# Node_Controller_v2.net
KiCad netlist of a schematic drawn in Altium Designer
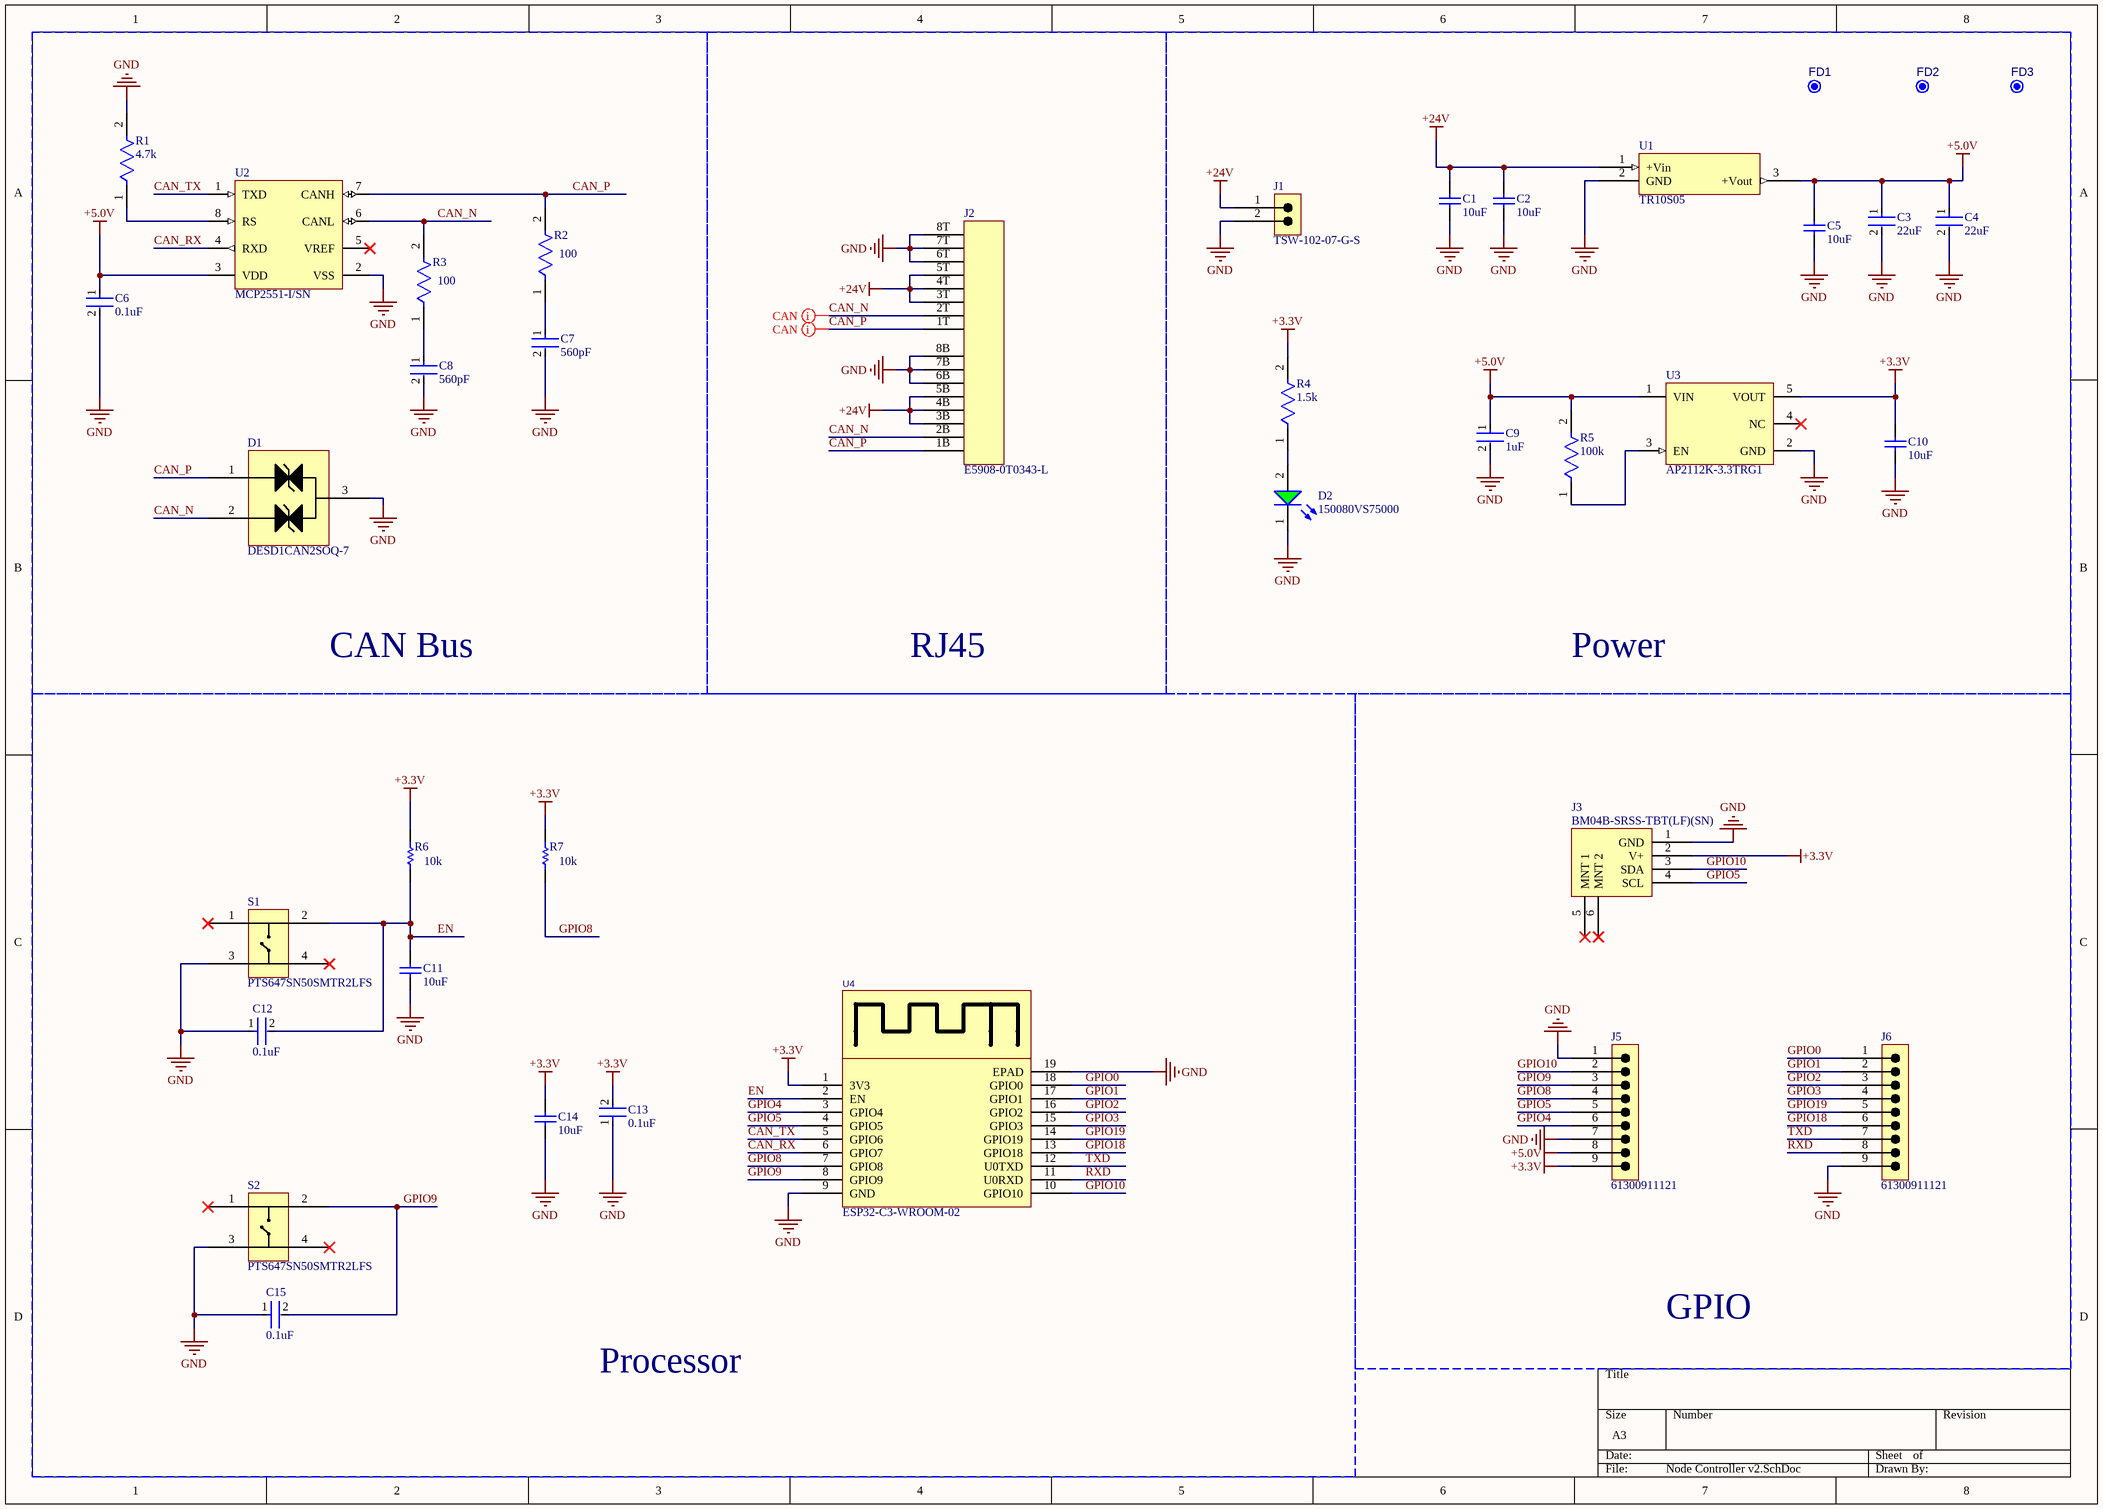
[diagram p0: Node Controller v2.SchDoc]

(export (version "E")
  (design (tool "Eeschema 10.0.6"))
  (components
    (comp (ref "C1")
      (value "10uF")
      (footprint "CAPC2013X145X50ML20T25")
      (libsource (lib "C0514760 C0514760") (part "CAP-NP-2"))
    )
    (comp (ref "C2")
      (value "10uF")
      (footprint "CAPC2013X145X50ML20T25")
      (libsource (lib "C0514760 C0514760") (part "CAP-NP-2"))
    )
    (comp (ref "C3")
      (value "22uF")
      (footprint "FP-GMC21R-IPC_B")
      (libsource (lib "C0514760 C0514760") (part "b4654b650e69147ec39a6b967a45e02"))
    )
    (comp (ref "C4")
      (value "22uF")
      (footprint "FP-GMC21R-IPC_B")
      (libsource (lib "C0514760 C0514760") (part "b4654b650e69147ec39a6b967a45e02"))
    )
    (comp (ref "C5")
      (value "10uF")
      (footprint "CAPC2013X145X50ML20T25")
      (libsource (lib "C0514760 C0514760") (part "CAP-NP-2"))
    )
    (comp (ref "C6")
      (value "0.1uF")
      (footprint "FP-CC0603-DA-IPC_A")
      (libsource (lib "C0514760 C0514760") (part "11868f565c42a9108669ba33697ecf6"))
    )
    (comp (ref "C7")
      (value "560pF")
      (footprint "FP-CC0805-0_85-IPC_A")
      (libsource (lib "C0514760 C0514760") (part "11868f565c42a9108669ba33697ecf6"))
    )
    (comp (ref "C8")
      (value "560pF")
      (footprint "FP-CC0805-0_85-IPC_A")
      (libsource (lib "C0514760 C0514760") (part "11868f565c42a9108669ba33697ecf6"))
    )
    (comp (ref "C9")
      (value "1uF")
      (footprint "FP-CL21-IPC_A")
      (libsource (lib "C0514760 C0514760") (part "b4654b650e69147ec39a6b967a45e02"))
    )
    (comp (ref "C10")
      (value "10uF")
      (footprint "CAPC2013X145X50ML20T25")
      (libsource (lib "C0514760 C0514760") (part "CAP-NP-2"))
    )
    (comp (ref "C11")
      (value "10uF")
      (footprint "CAPC2013X145X50ML20T25")
      (libsource (lib "C0514760 C0514760") (part "CAP-NP-2"))
    )
    (comp (ref "C12")
      (value "0.1uF")
      (footprint "FP-CC0603-DA-IPC_A")
      (libsource (lib "C0514760 C0514760") (part "11868f565c42a9108669ba33697ecf6"))
    )
    (comp (ref "C13")
      (value "0.1uF")
      (footprint "FP-CC0603-DA-IPC_A")
      (libsource (lib "C0514760 C0514760") (part "11868f565c42a9108669ba33697ecf6"))
    )
    (comp (ref "C14")
      (value "10uF")
      (footprint "CAPC2013X145X50ML20T25")
      (libsource (lib "C0514760 C0514760") (part "CAP-NP-2"))
    )
    (comp (ref "C15")
      (value "0.1uF")
      (footprint "FP-CC0603-DA-IPC_A")
      (libsource (lib "C0514760 C0514760") (part "11868f565c42a9108669ba33697ecf6"))
    )
    (comp (ref "D1")
      (value "DESD1CAN2SOQ-7")
      (footprint "SOT95P245X110-3N")
      (description "Trans Voltage Suppressor Diode, 200W, 24V V(RWM), Bidirectional, 2 Element, Silicon")
      (libsource (lib "C0514760 C0514760") (part "DESD1CAN2SOQ-7-Symbol-1"))
    )
    (comp (ref "D2")
      (value "150080VS75000")
      (footprint "WL-SMCW_0805_150080xx75000")
      (description "Single Color LED, Bright Green, Water Clear, 1.4mm")
      (libsource (lib "C0514760 C0514760") (part "LED_Green_2A-1K"))
    )
    (comp (ref "FD1")
      (value "JLC FID1X2R")
      (footprint "FID1X2R")
      (description "Fiducial - Round 1x2mm")
      (libsource (lib "C0514760 C0514760") (part "CMP-00134-2"))
    )
    (comp (ref "FD2")
      (value "JLC FID1X2R")
      (footprint "FID1X2R")
      (description "Fiducial - Round 1x2mm")
      (libsource (lib "C0514760 C0514760") (part "CMP-00134-2"))
    )
    (comp (ref "FD3")
      (value "JLC FID1X2R")
      (footprint "FID1X2R")
      (description "Fiducial - Round 1x2mm")
      (libsource (lib "C0514760 C0514760") (part "CMP-00134-2"))
    )
    (comp (ref "J1")
      (value "TSW-102-07-G-S")
      (footprint "FP-TSW-102-07-G-S-MFG")
      (libsource (lib "C0514760 C0514760") (part "3bc925449376181038e59eaffc5286c"))
    )
    (comp (ref "J2")
      (value "E5908-0T0343-L")
      (footprint "E5908-0T0343-L-Footprint-1")
      (description "Telecom and Datacom Connector, 16 Contact(s), Female, Right Angle, Solder Terminal, Jack")
      (libsource (lib "C0514760 C0514760") (part "E5908-0T0343-L-Symbol-1"))
    )
    (comp (ref "J3")
      (value "BM04B-SRSS-TBT(LF)(SN)")
      (footprint "FP-BM04B-SRSS-TBT_LF_SN-MFG")
      (description "1.0mm Pitch, Ultra-Compact, Low Profile Design, Interchangeable Shrouded Header")
      (libsource (lib "C0514760 C0514760") (part "8e3688c4b118bffc0dd9b7401e414ba"))
    )
    (comp (ref "J5")
      (value "61300911121")
      (footprint "61300911121")
      (libsource (lib "C0514760 C0514760") (part "Header_Male_1R_09P"))
    )
    (comp (ref "J6")
      (value "61300911121")
      (footprint "61300911121")
      (libsource (lib "C0514760 C0514760") (part "Header_Male_1R_09P"))
    )
    (comp (ref "R1")
      (value "4.7k")
      (footprint "FP-RT0805-IPC_A")
      (description "Fixed Resistor, Thin Film, 0.125W, 4700ohm, 150V, 1% +/-Tol, 50ppm/Cel, Surface Mount, 0805")
      (fields (field (name "TOLERANCE") "1%") (field (name "POWER") "125mW"))
      (libsource (lib "C0514760 C0514760") (part "1029c3af85768c4190bb7ad29bc67b5"))
    )
    (comp (ref "R2")
      (value "100")
      (footprint "FP-RT0805-0_6-IPC_A")
      (description "Fixed Resistor, Thin Film, 0.125W, 100ohm, 150V, 0.1% +/-Tol, 25ppm/Cel, Surface Mount, 0805")
      (fields (field (name "POWER") "125mW") (field (name "TOLERANCE") "0.1%"))
      (libsource (lib "C0514760 C0514760") (part "1029c3af85768c4190bb7ad29bc67b5"))
    )
    (comp (ref "R3")
      (value "100")
      (footprint "FP-RT0805-0_6-IPC_A")
      (description "Fixed Resistor, Thin Film, 0.125W, 100ohm, 150V, 0.1% +/-Tol, 25ppm/Cel, Surface Mount, 0805")
      (fields (field (name "POWER") "125mW") (field (name "TOLERANCE") "0.1%"))
      (libsource (lib "C0514760 C0514760") (part "1029c3af85768c4190bb7ad29bc67b5"))
    )
    (comp (ref "R4")
      (value "1.5k")
      (footprint "FP-RT0805-IPC_A")
      (description "Fixed Resistor, Thin Film, 0.125W, 1500ohm, 150V, 1% +/-Tol, 50ppm/Cel, Surface Mount, 0805")
      (fields (field (name "POWER") "125mW") (field (name "TOLERANCE") "1%"))
      (libsource (lib "C0514760 C0514760") (part "1029c3af85768c4190bb7ad29bc67b5"))
    )
    (comp (ref "R5")
      (value "100k")
      (footprint "FP-RT0805-IPC_A")
      (description "Fixed Resistor, Thin Film, 0.125W, 100000ohm, 150V, 1% +/-Tol, 50ppm/Cel, Surface Mount, 0805")
      (fields (field (name "TOLERANCE") "1%") (field (name "POWER") "125mW"))
      (libsource (lib "C0514760 C0514760") (part "1029c3af85768c4190bb7ad29bc67b5"))
    )
    (comp (ref "R6")
      (value "10k")
      (footprint "RESC2013X60X35ML10T20")
      (fields (field (name "TOLERANCE") "1%") (field (name "POWER") "125mW"))
      (libsource (lib "C0514760 C0514760") (part "RES"))
    )
    (comp (ref "R7")
      (value "10k")
      (footprint "RESC2013X60X35ML10T20")
      (fields (field (name "TOLERANCE") "1%") (field (name "POWER") "125mW"))
      (libsource (lib "C0514760 C0514760") (part "RES"))
    )
    (comp (ref "S1")
      (value "PTS647SN50SMTR2LFS")
      (footprint "PTS647SN50SMTR2LFS-Footprint-1")
      (libsource (lib "C0514760 C0514760") (part "PTS647SN50SMTR2LFS-Symbol-1"))
    )
    (comp (ref "S2")
      (value "PTS647SN50SMTR2LFS")
      (footprint "PTS647SN50SMTR2LFS-Footprint-1")
      (libsource (lib "C0514760 C0514760") (part "PTS647SN50SMTR2LFS-Symbol-1"))
    )
    (comp (ref "U1")
      (value "TR10S05")
      (footprint "TR10S05-Footprint-1")
      (description "DC-DC Regulated Power Supply Module")
      (libsource (lib "C0514760 C0514760") (part "TR10S05-Symbol-1"))
    )
    (comp (ref "U2")
      (value "MCP2551-I/SN")
      (footprint "MCHP-SN8_V")
      (description "CAN Transceiver, 1-Trnsvr, PDSO8")
      (libsource (lib "C0514760 C0514760") (part "MCHP-MCP2551-SN8"))
    )
    (comp (ref "U3")
      (value "AP2112K-3.3TRG1")
      (footprint "FP-SOT25-IPC_B")
      (description "Fixed Positive LDO Regulator, 3.3V, 0.4V Dropout, CMOS, PDSO5")
      (libsource (lib "C0514760 C0514760") (part "c8ab751aee5229183125ab046a11caa"))
    )
    (comp (ref "U4")
      (value "ESP32-C3-WROOM-02")
      (footprint "ESP32-C3-WROOM-02")
      (libsource (lib "C0514760 C0514760") (part "ESP32-C3-WROOM-02"))
    )
  )
  (nets
    (net (code "1") (name "+3.3V") (class "Default")
      (node (ref "C10") (pin "2") (pinfunction "2_2") (pintype "passive"))
      (node (ref "C13") (pin "2") (pinfunction "2_2") (pintype "passive"))
      (node (ref "C14") (pin "2") (pinfunction "2_2") (pintype "passive"))
      (node (ref "J3") (pin "2") (pinfunction "V+_2") (pintype "passive"))
      (node (ref "J5") (pin "9") (pinfunction "9_9") (pintype "passive"))
      (node (ref "R4") (pin "2") (pinfunction "2_2") (pintype "passive"))
      (node (ref "R6") (pin "2") (pinfunction "2_2") (pintype "passive"))
      (node (ref "R7") (pin "2") (pinfunction "2_2") (pintype "passive"))
      (node (ref "U3") (pin "5") (pinfunction "VOUT_5") (pintype "power_in"))
      (node (ref "U4") (pin "1") (pinfunction "3V3_1") (pintype "passive"))
    )
    (net (code "2") (name "+5.0V") (class "Default")
      (node (ref "C3") (pin "1") (pinfunction "1_1") (pintype "passive"))
      (node (ref "C4") (pin "1") (pinfunction "1_1") (pintype "passive"))
      (node (ref "C5") (pin "2") (pinfunction "2_2") (pintype "passive"))
      (node (ref "C6") (pin "1") (pinfunction "1_1") (pintype "passive"))
      (node (ref "C9") (pin "1") (pinfunction "1_1") (pintype "passive"))
      (node (ref "J5") (pin "8") (pinfunction "8_8") (pintype "passive"))
      (node (ref "R5") (pin "2") (pinfunction "2_2") (pintype "passive"))
      (node (ref "U1") (pin "3") (pinfunction "+Vout_3") (pintype "output"))
      (node (ref "U2") (pin "3") (pinfunction "VDD_3") (pintype "power_in"))
      (node (ref "U3") (pin "1") (pinfunction "VIN_1") (pintype "power_in"))
    )
    (net (code "3") (name "+24V") (class "Default")
      (node (ref "C1") (pin "2") (pinfunction "2_2") (pintype "passive"))
      (node (ref "C2") (pin "2") (pinfunction "2_2") (pintype "passive"))
      (node (ref "J1") (pin "1") (pinfunction "1_1") (pintype "passive"))
      (node (ref "J2") (pin "3B") (pinfunction "3B_3B") (pintype "passive"))
      (node (ref "J2") (pin "3T") (pinfunction "3T_3T") (pintype "passive"))
      (node (ref "J2") (pin "4B") (pinfunction "4B_4B") (pintype "passive"))
      (node (ref "J2") (pin "4T") (pinfunction "4T_4T") (pintype "passive"))
      (node (ref "J2") (pin "5B") (pinfunction "5B_5B") (pintype "passive"))
      (node (ref "J2") (pin "5T") (pinfunction "5T_5T") (pintype "passive"))
      (node (ref "U1") (pin "1") (pinfunction "+Vin_1") (pintype "input"))
    )
    (net (code "4") (name "/CAN_N") (class "Default")
      (node (ref "D1") (pin "2") (pinfunction "2_2") (pintype "passive"))
      (node (ref "J2") (pin "2B") (pinfunction "2B_2B") (pintype "passive"))
      (node (ref "J2") (pin "2T") (pinfunction "2T_2T") (pintype "passive"))
      (node (ref "R3") (pin "2") (pinfunction "2_2") (pintype "passive"))
      (node (ref "U2") (pin "6") (pinfunction "CANL_6") (pintype "bidirectional"))
    )
    (net (code "5") (name "/CAN_P") (class "Default")
      (node (ref "D1") (pin "1") (pinfunction "1_1") (pintype "passive"))
      (node (ref "J2") (pin "1B") (pinfunction "1B_1B") (pintype "passive"))
      (node (ref "J2") (pin "1T") (pinfunction "1T_1T") (pintype "passive"))
      (node (ref "R2") (pin "2") (pinfunction "2_2") (pintype "passive"))
      (node (ref "U2") (pin "7") (pinfunction "CANH_7") (pintype "bidirectional"))
    )
    (net (code "6") (name "/CAN_RX") (class "Default")
      (node (ref "U2") (pin "4") (pinfunction "RXD_4") (pintype "output"))
      (node (ref "U4") (pin "6") (pinfunction "GPIO7_6") (pintype "passive"))
    )
    (net (code "7") (name "/CAN_TX") (class "Default")
      (node (ref "U2") (pin "1") (pinfunction "TXD_1") (pintype "input"))
      (node (ref "U4") (pin "5") (pinfunction "GPIO6_5") (pintype "passive"))
    )
    (net (code "8") (name "/EN") (class "Default")
      (node (ref "C11") (pin "2") (pinfunction "2_2") (pintype "passive"))
      (node (ref "C12") (pin "2") (pinfunction "2_2") (pintype "passive"))
      (node (ref "R6") (pin "1") (pinfunction "1_1") (pintype "passive"))
      (node (ref "S1") (pin "2") (pinfunction "2_2") (pintype "passive"))
      (node (ref "U4") (pin "2") (pinfunction "EN_2") (pintype "passive"))
    )
    (net (code "9") (name "/GPIO0") (class "Default")
      (node (ref "J6") (pin "1") (pinfunction "1_1") (pintype "passive"))
      (node (ref "U4") (pin "18") (pinfunction "GPIO0_18") (pintype "passive"))
    )
    (net (code "10") (name "/GPIO1") (class "Default")
      (node (ref "J6") (pin "2") (pinfunction "2_2") (pintype "passive"))
      (node (ref "U4") (pin "17") (pinfunction "GPIO1_17") (pintype "passive"))
    )
    (net (code "11") (name "/GPIO2") (class "Default")
      (node (ref "J6") (pin "3") (pinfunction "3_3") (pintype "passive"))
      (node (ref "U4") (pin "16") (pinfunction "GPIO2_16") (pintype "passive"))
    )
    (net (code "12") (name "/GPIO3") (class "Default")
      (node (ref "J6") (pin "4") (pinfunction "4_4") (pintype "passive"))
      (node (ref "U4") (pin "15") (pinfunction "GPIO3_15") (pintype "passive"))
    )
    (net (code "13") (name "/GPIO4") (class "Default")
      (node (ref "J5") (pin "6") (pinfunction "6_6") (pintype "passive"))
      (node (ref "U4") (pin "3") (pinfunction "GPIO4_3") (pintype "passive"))
    )
    (net (code "14") (name "/GPIO5") (class "Default")
      (node (ref "J3") (pin "4") (pinfunction "SCL_4") (pintype "passive"))
      (node (ref "J5") (pin "5") (pinfunction "5_5") (pintype "passive"))
      (node (ref "U4") (pin "4") (pinfunction "GPIO5_4") (pintype "passive"))
    )
    (net (code "15") (name "/GPIO8") (class "Default")
      (node (ref "J5") (pin "4") (pinfunction "4_4") (pintype "passive"))
      (node (ref "R7") (pin "1") (pinfunction "1_1") (pintype "passive"))
      (node (ref "U4") (pin "7") (pinfunction "GPIO8_7") (pintype "passive"))
    )
    (net (code "16") (name "/GPIO9") (class "Default")
      (node (ref "C15") (pin "2") (pinfunction "2_2") (pintype "passive"))
      (node (ref "J5") (pin "3") (pinfunction "3_3") (pintype "passive"))
      (node (ref "S2") (pin "2") (pinfunction "2_2") (pintype "passive"))
      (node (ref "U4") (pin "8") (pinfunction "GPIO9_8") (pintype "passive"))
    )
    (net (code "17") (name "/GPIO10") (class "Default")
      (node (ref "J3") (pin "3") (pinfunction "SDA_3") (pintype "passive"))
      (node (ref "J5") (pin "2") (pinfunction "2_2") (pintype "passive"))
      (node (ref "U4") (pin "10") (pinfunction "GPIO10_10") (pintype "passive"))
    )
    (net (code "18") (name "/GPIO18") (class "Default")
      (node (ref "J6") (pin "6") (pinfunction "6_6") (pintype "passive"))
      (node (ref "U4") (pin "13") (pinfunction "GPIO18_13") (pintype "passive"))
    )
    (net (code "19") (name "/GPIO19") (class "Default")
      (node (ref "J6") (pin "5") (pinfunction "5_5") (pintype "passive"))
      (node (ref "U4") (pin "14") (pinfunction "GPIO19_14") (pintype "passive"))
    )
    (net (code "20") (name "/RXD") (class "Default")
      (node (ref "J6") (pin "8") (pinfunction "8_8") (pintype "passive"))
      (node (ref "U4") (pin "11") (pinfunction "U0RXD_11") (pintype "passive"))
    )
    (net (code "21") (name "/TXD") (class "Default")
      (node (ref "J6") (pin "7") (pinfunction "7_7") (pintype "passive"))
      (node (ref "U4") (pin "12") (pinfunction "U0TXD_12") (pintype "passive"))
    )
    (net (code "22") (name "GND") (class "Default")
      (node (ref "C1") (pin "1") (pinfunction "1_1") (pintype "passive"))
      (node (ref "C10") (pin "1") (pinfunction "1_1") (pintype "passive"))
      (node (ref "C11") (pin "1") (pinfunction "1_1") (pintype "passive"))
      (node (ref "C12") (pin "1") (pinfunction "1_1") (pintype "passive"))
      (node (ref "C13") (pin "1") (pinfunction "1_1") (pintype "passive"))
      (node (ref "C14") (pin "1") (pinfunction "1_1") (pintype "passive"))
      (node (ref "C15") (pin "1") (pinfunction "1_1") (pintype "passive"))
      (node (ref "C2") (pin "1") (pinfunction "1_1") (pintype "passive"))
      (node (ref "C3") (pin "2") (pinfunction "2_2") (pintype "passive"))
      (node (ref "C4") (pin "2") (pinfunction "2_2") (pintype "passive"))
      (node (ref "C5") (pin "1") (pinfunction "1_1") (pintype "passive"))
      (node (ref "C6") (pin "2") (pinfunction "2_2") (pintype "passive"))
      (node (ref "C7") (pin "2") (pinfunction "2_2") (pintype "passive"))
      (node (ref "C8") (pin "2") (pinfunction "2_2") (pintype "passive"))
      (node (ref "C9") (pin "2") (pinfunction "2_2") (pintype "passive"))
      (node (ref "D1") (pin "3") (pinfunction "3_3") (pintype "passive"))
      (node (ref "D2") (pin "1") (pinfunction "K_1") (pintype "passive"))
      (node (ref "J1") (pin "2") (pinfunction "2_2") (pintype "passive"))
      (node (ref "J2") (pin "6B") (pinfunction "6B_6B") (pintype "passive"))
      (node (ref "J2") (pin "6T") (pinfunction "6T_6T") (pintype "passive"))
      (node (ref "J2") (pin "7B") (pinfunction "7B_7B") (pintype "passive"))
      (node (ref "J2") (pin "7T") (pinfunction "7T_7T") (pintype "passive"))
      (node (ref "J2") (pin "8B") (pinfunction "8B_8B") (pintype "passive"))
      (node (ref "J2") (pin "8T") (pinfunction "8T_8T") (pintype "passive"))
      (node (ref "J3") (pin "1") (pinfunction "GND_1") (pintype "passive"))
      (node (ref "J5") (pin "1") (pinfunction "1_1") (pintype "passive"))
      (node (ref "J5") (pin "7") (pinfunction "7_7") (pintype "passive"))
      (node (ref "J6") (pin "9") (pinfunction "9_9") (pintype "passive"))
      (node (ref "R1") (pin "2") (pinfunction "2_2") (pintype "passive"))
      (node (ref "S1") (pin "3") (pinfunction "3_3") (pintype "passive"))
      (node (ref "S2") (pin "3") (pinfunction "3_3") (pintype "passive"))
      (node (ref "U1") (pin "2") (pinfunction "GND_2") (pintype "power_in"))
      (node (ref "U2") (pin "2") (pinfunction "VSS_2") (pintype "power_in"))
      (node (ref "U3") (pin "2") (pinfunction "GND_2") (pintype "power_in"))
      (node (ref "U4") (pin "19") (pinfunction "EPAD_19") (pintype "passive"))
      (node (ref "U4") (pin "9") (pinfunction "GND_9") (pintype "passive"))
    )
    (net (code "23") (name "Net-(C7-Pad1)") (class "Default")
      (node (ref "C7") (pin "1") (pinfunction "1_1") (pintype "passive"))
      (node (ref "R2") (pin "1") (pinfunction "1_1") (pintype "passive"))
    )
    (net (code "24") (name "Net-(C8-Pad1)") (class "Default")
      (node (ref "C8") (pin "1") (pinfunction "1_1") (pintype "passive"))
      (node (ref "R3") (pin "1") (pinfunction "1_1") (pintype "passive"))
    )
    (net (code "25") (name "Net-(D2-A)") (class "Default")
      (node (ref "D2") (pin "2") (pinfunction "A_2") (pintype "passive"))
      (node (ref "R4") (pin "1") (pinfunction "1_1") (pintype "passive"))
    )
    (net (code "26") (name "Net-(U2-RS)") (class "Default")
      (node (ref "R1") (pin "1") (pinfunction "1_1") (pintype "passive"))
      (node (ref "U2") (pin "8") (pinfunction "RS_8") (pintype "input"))
    )
    (net (code "27") (name "Net-(U3-EN)") (class "Default")
      (node (ref "R5") (pin "1") (pinfunction "1_1") (pintype "passive"))
      (node (ref "U3") (pin "3") (pinfunction "EN_3") (pintype "input"))
    )
    (net (code "28") (name "unconnected-(J3-MNT_1-Pad5)") (class "Default")
      (node (ref "J3") (pin "5") (pinfunction "MNT_1_5") (pintype "passive+no_connect"))
    )
    (net (code "29") (name "unconnected-(J3-MNT_2-Pad6)") (class "Default")
      (node (ref "J3") (pin "6") (pinfunction "MNT_2_6") (pintype "passive+no_connect"))
    )
    (net (code "30") (name "unconnected-(S1-Pad1)") (class "Default")
      (node (ref "S1") (pin "1") (pinfunction "1_1") (pintype "passive+no_connect"))
    )
    (net (code "31") (name "unconnected-(S1-Pad4)") (class "Default")
      (node (ref "S1") (pin "4") (pinfunction "4_4") (pintype "passive+no_connect"))
    )
    (net (code "32") (name "unconnected-(S2-Pad1)") (class "Default")
      (node (ref "S2") (pin "1") (pinfunction "1_1") (pintype "passive+no_connect"))
    )
    (net (code "33") (name "unconnected-(S2-Pad4)") (class "Default")
      (node (ref "S2") (pin "4") (pinfunction "4_4") (pintype "passive+no_connect"))
    )
    (net (code "34") (name "unconnected-(U2-VREF-Pad5)") (class "Default")
      (node (ref "U2") (pin "5") (pinfunction "VREF_5") (pintype "power_in+no_connect"))
    )
    (net (code "35") (name "unconnected-(U3-NC-Pad4)") (class "Default")
      (node (ref "U3") (pin "4") (pinfunction "NC_4") (pintype "passive+no_connect"))
    )
    (net (code "36") (name "unconnected-(U4-GND-Pad9)") (class "Default")
      (node (ref "U4") (pin "9") (pinfunction "GND_9") (pintype "passive"))
    )
  )
)
